# PATHOS_FPGA_Power.net
KiCad netlist of a schematic drawn in Altium Designer
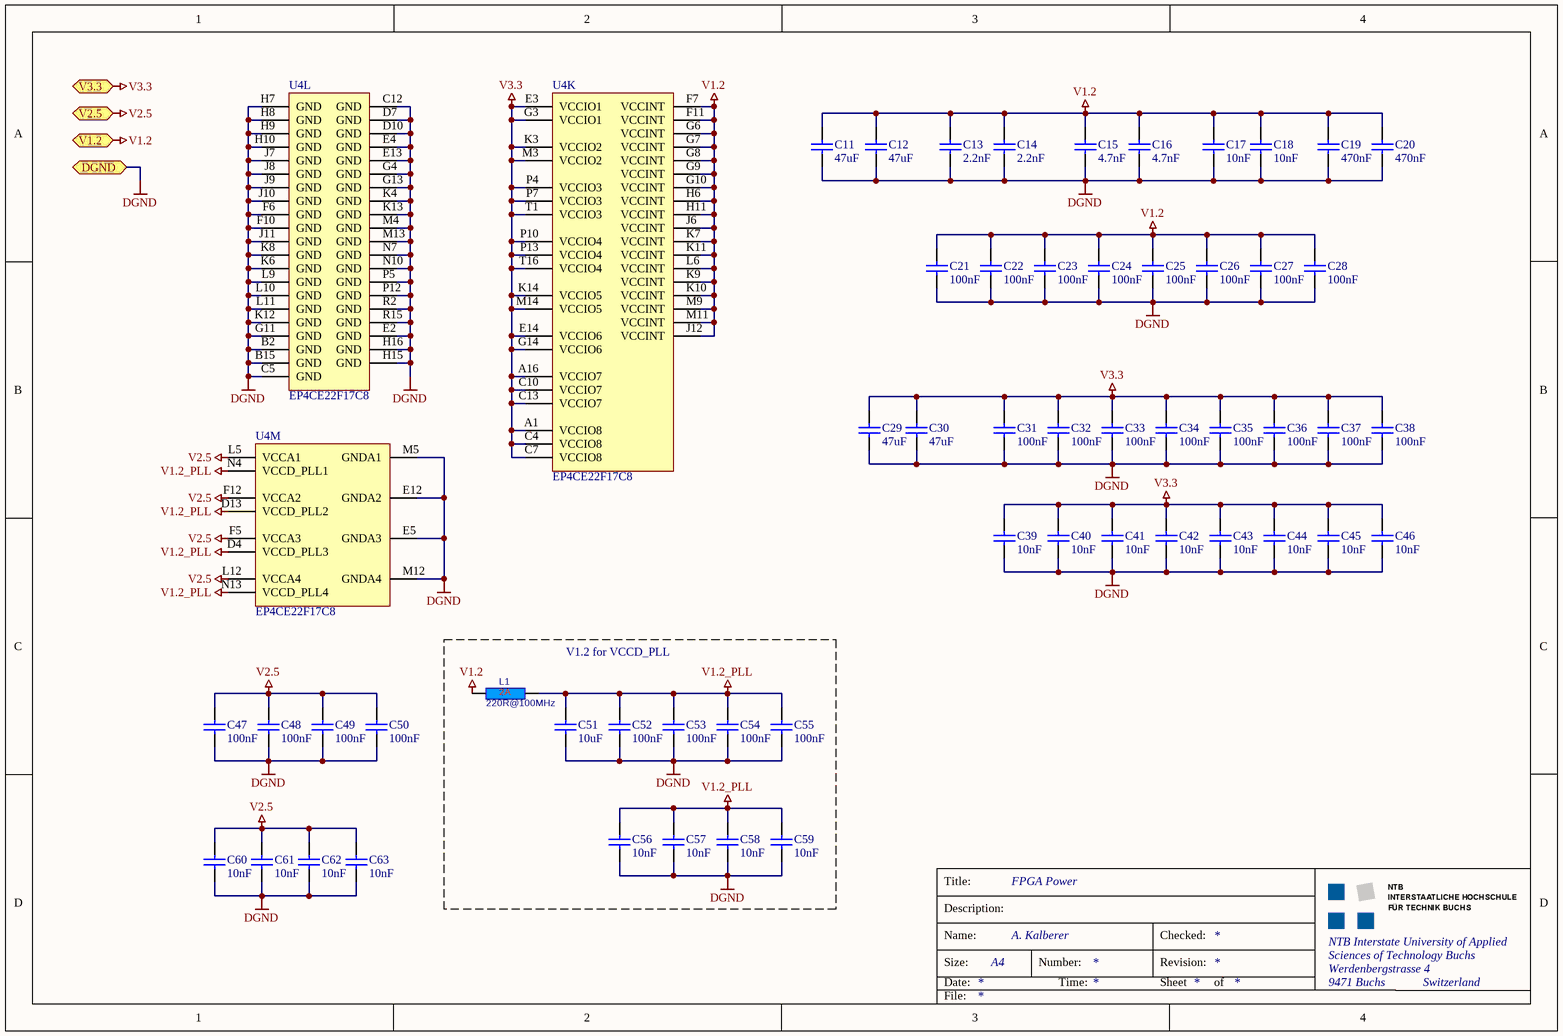
[diagram p0: PATHOS_FPGA_Power.SchDoc]

(export (version "E")
  (design (tool "Eeschema 10.0.6"))
  (components
    (comp (ref "C11")
      (value "47uF")
      (footprint "0805_3D")
      (description "Capacitor")
      (fields (field (name "#PUBLISHER") "Dr. A. Heinzelmann"))
      (libsource (lib "EFS_Sensorboard") (part "C"))
    )
    (comp (ref "C12")
      (value "47uF")
      (footprint "0805_3D")
      (description "Capacitor")
      (fields (field (name "#PUBLISHER") "Dr. A. Heinzelmann"))
      (libsource (lib "EFS_Sensorboard") (part "C"))
    )
    (comp (ref "C13")
      (value "2.2nF")
      (footprint "0402_3D")
      (description "Capacitor")
      (fields (field (name "#PUBLISHER") "Dr. A. Heinzelmann"))
      (libsource (lib "EFS_Sensorboard") (part "C"))
    )
    (comp (ref "C14")
      (value "2.2nF")
      (footprint "0402_3D")
      (description "Capacitor")
      (fields (field (name "#PUBLISHER") "Dr. A. Heinzelmann"))
      (libsource (lib "EFS_Sensorboard") (part "C"))
    )
    (comp (ref "C15")
      (value "4.7nF")
      (footprint "0402_3D")
      (description "Capacitor")
      (fields (field (name "#PUBLISHER") "Dr. A. Heinzelmann"))
      (libsource (lib "EFS_Sensorboard") (part "C"))
    )
    (comp (ref "C16")
      (value "4.7nF")
      (footprint "0402_3D")
      (description "Capacitor")
      (fields (field (name "#PUBLISHER") "Dr. A. Heinzelmann"))
      (libsource (lib "EFS_Sensorboard") (part "C"))
    )
    (comp (ref "C17")
      (value "10nF")
      (footprint "0402_3D")
      (description "Capacitor")
      (fields (field (name "#PUBLISHER") "Dr. A. Heinzelmann"))
      (libsource (lib "EFS_Sensorboard") (part "C"))
    )
    (comp (ref "C18")
      (value "10nF")
      (footprint "0402_3D")
      (description "Capacitor")
      (fields (field (name "#PUBLISHER") "Dr. A. Heinzelmann"))
      (libsource (lib "EFS_Sensorboard") (part "C"))
    )
    (comp (ref "C19")
      (value "470nF")
      (footprint "0603_3D")
      (description "Capacitor")
      (fields (field (name "#PUBLISHER") "Dr. A. Heinzelmann"))
      (libsource (lib "EFS_Sensorboard") (part "C"))
    )
    (comp (ref "C20")
      (value "470nF")
      (footprint "0603_3D")
      (description "Capacitor")
      (fields (field (name "#PUBLISHER") "Dr. A. Heinzelmann"))
      (libsource (lib "EFS_Sensorboard") (part "C"))
    )
    (comp (ref "C21")
      (value "100nF")
      (footprint "0402_3D")
      (description "Capacitor")
      (fields (field (name "#PUBLISHER") "Dr. A. Heinzelmann"))
      (libsource (lib "EFS_Sensorboard") (part "C"))
    )
    (comp (ref "C22")
      (value "100nF")
      (footprint "0402_3D")
      (description "Capacitor")
      (fields (field (name "#PUBLISHER") "Dr. A. Heinzelmann"))
      (libsource (lib "EFS_Sensorboard") (part "C"))
    )
    (comp (ref "C23")
      (value "100nF")
      (footprint "0402_3D")
      (description "Capacitor")
      (fields (field (name "#PUBLISHER") "Dr. A. Heinzelmann"))
      (libsource (lib "EFS_Sensorboard") (part "C"))
    )
    (comp (ref "C24")
      (value "100nF")
      (footprint "0402_3D")
      (description "Capacitor")
      (fields (field (name "#PUBLISHER") "Dr. A. Heinzelmann"))
      (libsource (lib "EFS_Sensorboard") (part "C"))
    )
    (comp (ref "C25")
      (value "100nF")
      (footprint "0402_3D")
      (description "Capacitor")
      (fields (field (name "#PUBLISHER") "Dr. A. Heinzelmann"))
      (libsource (lib "EFS_Sensorboard") (part "C"))
    )
    (comp (ref "C26")
      (value "100nF")
      (footprint "0402_3D")
      (description "Capacitor")
      (fields (field (name "#PUBLISHER") "Dr. A. Heinzelmann"))
      (libsource (lib "EFS_Sensorboard") (part "C"))
    )
    (comp (ref "C27")
      (value "100nF")
      (footprint "0402_3D")
      (description "Capacitor")
      (fields (field (name "#PUBLISHER") "Dr. A. Heinzelmann"))
      (libsource (lib "EFS_Sensorboard") (part "C"))
    )
    (comp (ref "C28")
      (value "100nF")
      (footprint "0402_3D")
      (description "Capacitor")
      (fields (field (name "#PUBLISHER") "Dr. A. Heinzelmann"))
      (libsource (lib "EFS_Sensorboard") (part "C"))
    )
    (comp (ref "C29")
      (value "47uF")
      (footprint "0805_3D")
      (description "Capacitor")
      (fields (field (name "#PUBLISHER") "Dr. A. Heinzelmann"))
      (libsource (lib "EFS_Sensorboard") (part "C"))
    )
    (comp (ref "C30")
      (value "47uF")
      (footprint "0805_3D")
      (description "Capacitor")
      (fields (field (name "#PUBLISHER") "Dr. A. Heinzelmann"))
      (libsource (lib "EFS_Sensorboard") (part "C"))
    )
    (comp (ref "C31")
      (value "100nF")
      (footprint "0402_3D")
      (description "Capacitor")
      (fields (field (name "#PUBLISHER") "Dr. A. Heinzelmann"))
      (libsource (lib "EFS_Sensorboard") (part "C"))
    )
    (comp (ref "C32")
      (value "100nF")
      (footprint "0402_3D")
      (description "Capacitor")
      (fields (field (name "#PUBLISHER") "Dr. A. Heinzelmann"))
      (libsource (lib "EFS_Sensorboard") (part "C"))
    )
    (comp (ref "C33")
      (value "100nF")
      (footprint "0402_3D")
      (description "Capacitor")
      (fields (field (name "#PUBLISHER") "Dr. A. Heinzelmann"))
      (libsource (lib "EFS_Sensorboard") (part "C"))
    )
    (comp (ref "C34")
      (value "100nF")
      (footprint "0402_3D")
      (description "Capacitor")
      (fields (field (name "#PUBLISHER") "Dr. A. Heinzelmann"))
      (libsource (lib "EFS_Sensorboard") (part "C"))
    )
    (comp (ref "C35")
      (value "100nF")
      (footprint "0402_3D")
      (description "Capacitor")
      (fields (field (name "#PUBLISHER") "Dr. A. Heinzelmann"))
      (libsource (lib "EFS_Sensorboard") (part "C"))
    )
    (comp (ref "C36")
      (value "100nF")
      (footprint "0402_3D")
      (description "Capacitor")
      (fields (field (name "#PUBLISHER") "Dr. A. Heinzelmann"))
      (libsource (lib "EFS_Sensorboard") (part "C"))
    )
    (comp (ref "C37")
      (value "100nF")
      (footprint "0402_3D")
      (description "Capacitor")
      (fields (field (name "#PUBLISHER") "Dr. A. Heinzelmann"))
      (libsource (lib "EFS_Sensorboard") (part "C"))
    )
    (comp (ref "C38")
      (value "100nF")
      (footprint "0402_3D")
      (description "Capacitor")
      (fields (field (name "#PUBLISHER") "Dr. A. Heinzelmann"))
      (libsource (lib "EFS_Sensorboard") (part "C"))
    )
    (comp (ref "C39")
      (value "10nF")
      (footprint "0402_3D")
      (description "Capacitor")
      (fields (field (name "#PUBLISHER") "Dr. A. Heinzelmann"))
      (libsource (lib "EFS_Sensorboard") (part "C"))
    )
    (comp (ref "C40")
      (value "10nF")
      (footprint "0402_3D")
      (description "Capacitor")
      (fields (field (name "#PUBLISHER") "Dr. A. Heinzelmann"))
      (libsource (lib "EFS_Sensorboard") (part "C"))
    )
    (comp (ref "C41")
      (value "10nF")
      (footprint "0402_3D")
      (description "Capacitor")
      (fields (field (name "#PUBLISHER") "Dr. A. Heinzelmann"))
      (libsource (lib "EFS_Sensorboard") (part "C"))
    )
    (comp (ref "C42")
      (value "10nF")
      (footprint "0402_3D")
      (description "Capacitor")
      (fields (field (name "#PUBLISHER") "Dr. A. Heinzelmann"))
      (libsource (lib "EFS_Sensorboard") (part "C"))
    )
    (comp (ref "C43")
      (value "10nF")
      (footprint "0402_3D")
      (description "Capacitor")
      (fields (field (name "#PUBLISHER") "Dr. A. Heinzelmann"))
      (libsource (lib "EFS_Sensorboard") (part "C"))
    )
    (comp (ref "C44")
      (value "10nF")
      (footprint "0402_3D")
      (description "Capacitor")
      (fields (field (name "#PUBLISHER") "Dr. A. Heinzelmann"))
      (libsource (lib "EFS_Sensorboard") (part "C"))
    )
    (comp (ref "C45")
      (value "10nF")
      (footprint "0402_3D")
      (description "Capacitor")
      (fields (field (name "#PUBLISHER") "Dr. A. Heinzelmann"))
      (libsource (lib "EFS_Sensorboard") (part "C"))
    )
    (comp (ref "C46")
      (value "10nF")
      (footprint "0402_3D")
      (description "Capacitor")
      (fields (field (name "#PUBLISHER") "Dr. A. Heinzelmann"))
      (libsource (lib "EFS_Sensorboard") (part "C"))
    )
    (comp (ref "C47")
      (value "100nF")
      (footprint "0402_3D")
      (description "Capacitor")
      (fields (field (name "#PUBLISHER") "Dr. A. Heinzelmann"))
      (libsource (lib "EFS_Sensorboard") (part "C"))
    )
    (comp (ref "C48")
      (value "100nF")
      (footprint "0402_3D")
      (description "Capacitor")
      (fields (field (name "#PUBLISHER") "Dr. A. Heinzelmann"))
      (libsource (lib "EFS_Sensorboard") (part "C"))
    )
    (comp (ref "C49")
      (value "100nF")
      (footprint "0402_3D")
      (description "Capacitor")
      (fields (field (name "#PUBLISHER") "Dr. A. Heinzelmann"))
      (libsource (lib "EFS_Sensorboard") (part "C"))
    )
    (comp (ref "C50")
      (value "100nF")
      (footprint "0402_3D")
      (description "Capacitor")
      (fields (field (name "#PUBLISHER") "Dr. A. Heinzelmann"))
      (libsource (lib "EFS_Sensorboard") (part "C"))
    )
    (comp (ref "C51")
      (value "10uF")
      (footprint "0603_3D")
      (description "Capacitor")
      (fields (field (name "#PUBLISHER") "Dr. A. Heinzelmann"))
      (libsource (lib "EFS_Sensorboard") (part "C"))
    )
    (comp (ref "C52")
      (value "100nF")
      (footprint "0402_3D")
      (description "Capacitor")
      (fields (field (name "#PUBLISHER") "Dr. A. Heinzelmann"))
      (libsource (lib "EFS_Sensorboard") (part "C"))
    )
    (comp (ref "C53")
      (value "100nF")
      (footprint "0402_3D")
      (description "Capacitor")
      (fields (field (name "#PUBLISHER") "Dr. A. Heinzelmann"))
      (libsource (lib "EFS_Sensorboard") (part "C"))
    )
    (comp (ref "C54")
      (value "100nF")
      (footprint "0402_3D")
      (description "Capacitor")
      (fields (field (name "#PUBLISHER") "Dr. A. Heinzelmann"))
      (libsource (lib "EFS_Sensorboard") (part "C"))
    )
    (comp (ref "C55")
      (value "100nF")
      (footprint "0402_3D")
      (description "Capacitor")
      (fields (field (name "#PUBLISHER") "Dr. A. Heinzelmann"))
      (libsource (lib "EFS_Sensorboard") (part "C"))
    )
    (comp (ref "C56")
      (value "10nF")
      (footprint "0402_3D")
      (description "Capacitor")
      (fields (field (name "#PUBLISHER") "Dr. A. Heinzelmann"))
      (libsource (lib "EFS_Sensorboard") (part "C"))
    )
    (comp (ref "C57")
      (value "10nF")
      (footprint "0402_3D")
      (description "Capacitor")
      (fields (field (name "#PUBLISHER") "Dr. A. Heinzelmann"))
      (libsource (lib "EFS_Sensorboard") (part "C"))
    )
    (comp (ref "C58")
      (value "10nF")
      (footprint "0402_3D")
      (description "Capacitor")
      (fields (field (name "#PUBLISHER") "Dr. A. Heinzelmann"))
      (libsource (lib "EFS_Sensorboard") (part "C"))
    )
    (comp (ref "C59")
      (value "10nF")
      (footprint "0402_3D")
      (description "Capacitor")
      (fields (field (name "#PUBLISHER") "Dr. A. Heinzelmann"))
      (libsource (lib "EFS_Sensorboard") (part "C"))
    )
    (comp (ref "C60")
      (value "10nF")
      (footprint "0402_3D")
      (description "Capacitor")
      (fields (field (name "#PUBLISHER") "Dr. A. Heinzelmann"))
      (libsource (lib "EFS_Sensorboard") (part "C"))
    )
    (comp (ref "C61")
      (value "10nF")
      (footprint "0402_3D")
      (description "Capacitor")
      (fields (field (name "#PUBLISHER") "Dr. A. Heinzelmann"))
      (libsource (lib "EFS_Sensorboard") (part "C"))
    )
    (comp (ref "C62")
      (value "10nF")
      (footprint "0402_3D")
      (description "Capacitor")
      (fields (field (name "#PUBLISHER") "Dr. A. Heinzelmann"))
      (libsource (lib "EFS_Sensorboard") (part "C"))
    )
    (comp (ref "C63")
      (value "10nF")
      (footprint "0402_3D")
      (description "Capacitor")
      (fields (field (name "#PUBLISHER") "Dr. A. Heinzelmann"))
      (libsource (lib "EFS_Sensorboard") (part "C"))
    )
    (comp (ref "L1")
      (value "220R@100MHz")
      (footprint "0603_3D")
      (description "220R@100MHz 2A EMI FILTER")
      (fields (field (name "TOLERANCE") "25%"))
      (libsource (lib "Viola") (part "L-220R@100MHz-2A-25%-0603"))
    )
    (comp (ref "U4")
      (value "EP4CE22F17C8")
      (footprint "FBGA256")
      (fields (field (name "PUBLISHER") "Altium Limited"))
      (libsource (lib "EFS_Sensorboard") (part "EP4CE22F17C8"))
    )
  )
  (nets
    (net (code "1") (name "DGND") (class "Default")
      (node (ref "C11") (pin "1") (pinfunction "1_1") (pintype "passive"))
      (node (ref "C12") (pin "1") (pinfunction "1_1") (pintype "passive"))
      (node (ref "C13") (pin "1") (pinfunction "1_1") (pintype "passive"))
      (node (ref "C14") (pin "1") (pinfunction "1_1") (pintype "passive"))
      (node (ref "C15") (pin "1") (pinfunction "1_1") (pintype "passive"))
      (node (ref "C16") (pin "1") (pinfunction "1_1") (pintype "passive"))
      (node (ref "C17") (pin "1") (pinfunction "1_1") (pintype "passive"))
      (node (ref "C18") (pin "1") (pinfunction "1_1") (pintype "passive"))
      (node (ref "C19") (pin "1") (pinfunction "1_1") (pintype "passive"))
      (node (ref "C20") (pin "1") (pinfunction "1_1") (pintype "passive"))
      (node (ref "C21") (pin "1") (pinfunction "1_1") (pintype "passive"))
      (node (ref "C22") (pin "1") (pinfunction "1_1") (pintype "passive"))
      (node (ref "C23") (pin "1") (pinfunction "1_1") (pintype "passive"))
      (node (ref "C24") (pin "1") (pinfunction "1_1") (pintype "passive"))
      (node (ref "C25") (pin "1") (pinfunction "1_1") (pintype "passive"))
      (node (ref "C26") (pin "1") (pinfunction "1_1") (pintype "passive"))
      (node (ref "C27") (pin "1") (pinfunction "1_1") (pintype "passive"))
      (node (ref "C28") (pin "1") (pinfunction "1_1") (pintype "passive"))
      (node (ref "C29") (pin "1") (pinfunction "1_1") (pintype "passive"))
      (node (ref "C30") (pin "1") (pinfunction "1_1") (pintype "passive"))
      (node (ref "C31") (pin "1") (pinfunction "1_1") (pintype "passive"))
      (node (ref "C32") (pin "1") (pinfunction "1_1") (pintype "passive"))
      (node (ref "C33") (pin "1") (pinfunction "1_1") (pintype "passive"))
      (node (ref "C34") (pin "1") (pinfunction "1_1") (pintype "passive"))
      (node (ref "C35") (pin "1") (pinfunction "1_1") (pintype "passive"))
      (node (ref "C36") (pin "1") (pinfunction "1_1") (pintype "passive"))
      (node (ref "C37") (pin "1") (pinfunction "1_1") (pintype "passive"))
      (node (ref "C38") (pin "1") (pinfunction "1_1") (pintype "passive"))
      (node (ref "C39") (pin "1") (pinfunction "1_1") (pintype "passive"))
      (node (ref "C40") (pin "1") (pinfunction "1_1") (pintype "passive"))
      (node (ref "C41") (pin "1") (pinfunction "1_1") (pintype "passive"))
      (node (ref "C42") (pin "1") (pinfunction "1_1") (pintype "passive"))
      (node (ref "C43") (pin "1") (pinfunction "1_1") (pintype "passive"))
      (node (ref "C44") (pin "1") (pinfunction "1_1") (pintype "passive"))
      (node (ref "C45") (pin "1") (pinfunction "1_1") (pintype "passive"))
      (node (ref "C46") (pin "1") (pinfunction "1_1") (pintype "passive"))
      (node (ref "C47") (pin "1") (pinfunction "1_1") (pintype "passive"))
      (node (ref "C48") (pin "1") (pinfunction "1_1") (pintype "passive"))
      (node (ref "C49") (pin "1") (pinfunction "1_1") (pintype "passive"))
      (node (ref "C50") (pin "1") (pinfunction "1_1") (pintype "passive"))
      (node (ref "C51") (pin "1") (pinfunction "1_1") (pintype "passive"))
      (node (ref "C52") (pin "1") (pinfunction "1_1") (pintype "passive"))
      (node (ref "C53") (pin "1") (pinfunction "1_1") (pintype "passive"))
      (node (ref "C54") (pin "1") (pinfunction "1_1") (pintype "passive"))
      (node (ref "C55") (pin "1") (pinfunction "1_1") (pintype "passive"))
      (node (ref "C56") (pin "1") (pinfunction "1_1") (pintype "passive"))
      (node (ref "C57") (pin "1") (pinfunction "1_1") (pintype "passive"))
      (node (ref "C58") (pin "1") (pinfunction "1_1") (pintype "passive"))
      (node (ref "C59") (pin "1") (pinfunction "1_1") (pintype "passive"))
      (node (ref "C60") (pin "1") (pinfunction "1_1") (pintype "passive"))
      (node (ref "C61") (pin "1") (pinfunction "1_1") (pintype "passive"))
      (node (ref "C62") (pin "1") (pinfunction "1_1") (pintype "passive"))
      (node (ref "C63") (pin "1") (pinfunction "1_1") (pintype "passive"))
      (node (ref "U4") (pin "B15") (pinfunction "GND_B15") (pintype "power_in"))
      (node (ref "U4") (pin "B2") (pinfunction "GND_B2") (pintype "power_in"))
      (node (ref "U4") (pin "C12") (pinfunction "GND_C12") (pintype "power_in"))
      (node (ref "U4") (pin "C5") (pinfunction "GND_C5") (pintype "power_in"))
      (node (ref "U4") (pin "D10") (pinfunction "GND_D10") (pintype "power_in"))
      (node (ref "U4") (pin "D7") (pinfunction "GND_D7") (pintype "power_in"))
      (node (ref "U4") (pin "E12") (pinfunction "GNDA2_E12") (pintype "power_in"))
      (node (ref "U4") (pin "E13") (pinfunction "GND_E13") (pintype "power_in"))
      (node (ref "U4") (pin "E2") (pinfunction "GND_E2") (pintype "power_in"))
      (node (ref "U4") (pin "E4") (pinfunction "GND_E4") (pintype "power_in"))
      (node (ref "U4") (pin "E5") (pinfunction "GNDA3_E5") (pintype "power_in"))
      (node (ref "U4") (pin "F10") (pinfunction "GND_F10") (pintype "power_in"))
      (node (ref "U4") (pin "F6") (pinfunction "GND_F6") (pintype "power_in"))
      (node (ref "U4") (pin "G11") (pinfunction "GND_G11") (pintype "power_in"))
      (node (ref "U4") (pin "G13") (pinfunction "GND_G13") (pintype "power_in"))
      (node (ref "U4") (pin "G4") (pinfunction "GND_G4") (pintype "power_in"))
      (node (ref "U4") (pin "H10") (pinfunction "GND_H10") (pintype "power_in"))
      (node (ref "U4") (pin "H15") (pinfunction "GND_H15") (pintype "power_in"))
      (node (ref "U4") (pin "H16") (pinfunction "GND_H16") (pintype "power_in"))
      (node (ref "U4") (pin "H7") (pinfunction "GND_H7") (pintype "power_in"))
      (node (ref "U4") (pin "H8") (pinfunction "GND_H8") (pintype "power_in"))
      (node (ref "U4") (pin "H9") (pinfunction "GND_H9") (pintype "power_in"))
      (node (ref "U4") (pin "J10") (pinfunction "GND_J10") (pintype "power_in"))
      (node (ref "U4") (pin "J11") (pinfunction "GND_J11") (pintype "power_in"))
      (node (ref "U4") (pin "J7") (pinfunction "GND_J7") (pintype "power_in"))
      (node (ref "U4") (pin "J8") (pinfunction "GND_J8") (pintype "power_in"))
      (node (ref "U4") (pin "J9") (pinfunction "GND_J9") (pintype "power_in"))
      (node (ref "U4") (pin "K12") (pinfunction "GND_K12") (pintype "power_in"))
      (node (ref "U4") (pin "K13") (pinfunction "GND_K13") (pintype "power_in"))
      (node (ref "U4") (pin "K4") (pinfunction "GND_K4") (pintype "power_in"))
      (node (ref "U4") (pin "K6") (pinfunction "GND_K6") (pintype "power_in"))
      (node (ref "U4") (pin "K8") (pinfunction "GND_K8") (pintype "power_in"))
      (node (ref "U4") (pin "L10") (pinfunction "GND_L10") (pintype "power_in"))
      (node (ref "U4") (pin "L11") (pinfunction "GND_L11") (pintype "power_in"))
      (node (ref "U4") (pin "L9") (pinfunction "GND_L9") (pintype "power_in"))
      (node (ref "U4") (pin "M12") (pinfunction "GNDA4_M12") (pintype "power_in"))
      (node (ref "U4") (pin "M13") (pinfunction "GND_M13") (pintype "power_in"))
      (node (ref "U4") (pin "M4") (pinfunction "GND_M4") (pintype "power_in"))
      (node (ref "U4") (pin "M5") (pinfunction "GNDA1_M5") (pintype "power_in"))
      (node (ref "U4") (pin "N10") (pinfunction "GND_N10") (pintype "power_in"))
      (node (ref "U4") (pin "N7") (pinfunction "GND_N7") (pintype "power_in"))
      (node (ref "U4") (pin "P12") (pinfunction "GND_P12") (pintype "power_in"))
      (node (ref "U4") (pin "P5") (pinfunction "GND_P5") (pintype "power_in"))
      (node (ref "U4") (pin "R15") (pinfunction "GND_R15") (pintype "power_in"))
      (node (ref "U4") (pin "R2") (pinfunction "GND_R2") (pintype "power_in"))
    )
    (net (code "2") (name "V1.2") (class "Default")
      (node (ref "C11") (pin "2") (pinfunction "2_2") (pintype "passive"))
      (node (ref "C12") (pin "2") (pinfunction "2_2") (pintype "passive"))
      (node (ref "C13") (pin "2") (pinfunction "2_2") (pintype "passive"))
      (node (ref "C14") (pin "2") (pinfunction "2_2") (pintype "passive"))
      (node (ref "C15") (pin "2") (pinfunction "2_2") (pintype "passive"))
      (node (ref "C16") (pin "2") (pinfunction "2_2") (pintype "passive"))
      (node (ref "C17") (pin "2") (pinfunction "2_2") (pintype "passive"))
      (node (ref "C18") (pin "2") (pinfunction "2_2") (pintype "passive"))
      (node (ref "C19") (pin "2") (pinfunction "2_2") (pintype "passive"))
      (node (ref "C20") (pin "2") (pinfunction "2_2") (pintype "passive"))
      (node (ref "C21") (pin "2") (pinfunction "2_2") (pintype "passive"))
      (node (ref "C22") (pin "2") (pinfunction "2_2") (pintype "passive"))
      (node (ref "C23") (pin "2") (pinfunction "2_2") (pintype "passive"))
      (node (ref "C24") (pin "2") (pinfunction "2_2") (pintype "passive"))
      (node (ref "C25") (pin "2") (pinfunction "2_2") (pintype "passive"))
      (node (ref "C26") (pin "2") (pinfunction "2_2") (pintype "passive"))
      (node (ref "C27") (pin "2") (pinfunction "2_2") (pintype "passive"))
      (node (ref "C28") (pin "2") (pinfunction "2_2") (pintype "passive"))
      (node (ref "L1") (pin "1") (pinfunction "1_1") (pintype "passive"))
      (node (ref "U4") (pin "F11") (pinfunction "VCCINT_F11") (pintype "power_in"))
      (node (ref "U4") (pin "F7") (pinfunction "VCCINT_F7") (pintype "power_in"))
      (node (ref "U4") (pin "G10") (pinfunction "VCCINT_G10") (pintype "power_in"))
      (node (ref "U4") (pin "G6") (pinfunction "VCCINT_G6") (pintype "power_in"))
      (node (ref "U4") (pin "G7") (pinfunction "VCCINT_G7") (pintype "power_in"))
      (node (ref "U4") (pin "G8") (pinfunction "VCCINT_G8") (pintype "power_in"))
      (node (ref "U4") (pin "G9") (pinfunction "VCCINT_G9") (pintype "power_in"))
      (node (ref "U4") (pin "H11") (pinfunction "VCCINT_H11") (pintype "power_in"))
      (node (ref "U4") (pin "H6") (pinfunction "VCCINT_H6") (pintype "power_in"))
      (node (ref "U4") (pin "J12") (pinfunction "VCCINT_J12") (pintype "power_in"))
      (node (ref "U4") (pin "J6") (pinfunction "VCCINT_J6") (pintype "power_in"))
      (node (ref "U4") (pin "K10") (pinfunction "VCCINT_K10") (pintype "power_in"))
      (node (ref "U4") (pin "K11") (pinfunction "VCCINT_K11") (pintype "power_in"))
      (node (ref "U4") (pin "K7") (pinfunction "VCCINT_K7") (pintype "power_in"))
      (node (ref "U4") (pin "K9") (pinfunction "VCCINT_K9") (pintype "power_in"))
      (node (ref "U4") (pin "L6") (pinfunction "VCCINT_L6") (pintype "power_in"))
      (node (ref "U4") (pin "M11") (pinfunction "VCCINT_M11") (pintype "power_in"))
      (node (ref "U4") (pin "M9") (pinfunction "VCCINT_M9") (pintype "power_in"))
    )
    (net (code "3") (name "V1.2_PLL") (class "Default")
      (node (ref "C51") (pin "2") (pinfunction "2_2") (pintype "passive"))
      (node (ref "C52") (pin "2") (pinfunction "2_2") (pintype "passive"))
      (node (ref "C53") (pin "2") (pinfunction "2_2") (pintype "passive"))
      (node (ref "C54") (pin "2") (pinfunction "2_2") (pintype "passive"))
      (node (ref "C55") (pin "2") (pinfunction "2_2") (pintype "passive"))
      (node (ref "C56") (pin "2") (pinfunction "2_2") (pintype "passive"))
      (node (ref "C57") (pin "2") (pinfunction "2_2") (pintype "passive"))
      (node (ref "C58") (pin "2") (pinfunction "2_2") (pintype "passive"))
      (node (ref "C59") (pin "2") (pinfunction "2_2") (pintype "passive"))
      (node (ref "L1") (pin "2") (pinfunction "2_2") (pintype "passive"))
      (node (ref "U4") (pin "D13") (pinfunction "VCCD_PLL2_D13") (pintype "power_in"))
      (node (ref "U4") (pin "D4") (pinfunction "VCCD_PLL3_D4") (pintype "power_in"))
      (node (ref "U4") (pin "N13") (pinfunction "VCCD_PLL4_N13") (pintype "power_in"))
      (node (ref "U4") (pin "N4") (pinfunction "VCCD_PLL1_N4") (pintype "power_in"))
    )
    (net (code "4") (name "V2.5") (class "Default")
      (node (ref "C47") (pin "2") (pinfunction "2_2") (pintype "passive"))
      (node (ref "C48") (pin "2") (pinfunction "2_2") (pintype "passive"))
      (node (ref "C49") (pin "2") (pinfunction "2_2") (pintype "passive"))
      (node (ref "C50") (pin "2") (pinfunction "2_2") (pintype "passive"))
      (node (ref "C60") (pin "2") (pinfunction "2_2") (pintype "passive"))
      (node (ref "C61") (pin "2") (pinfunction "2_2") (pintype "passive"))
      (node (ref "C62") (pin "2") (pinfunction "2_2") (pintype "passive"))
      (node (ref "C63") (pin "2") (pinfunction "2_2") (pintype "passive"))
      (node (ref "U4") (pin "F12") (pinfunction "VCCA2_F12") (pintype "power_in"))
      (node (ref "U4") (pin "F5") (pinfunction "VCCA3_F5") (pintype "power_in"))
      (node (ref "U4") (pin "L12") (pinfunction "VCCA4_L12") (pintype "power_in"))
      (node (ref "U4") (pin "L5") (pinfunction "VCCA1_L5") (pintype "power_in"))
    )
    (net (code "5") (name "V3.3") (class "Default")
      (node (ref "C29") (pin "2") (pinfunction "2_2") (pintype "passive"))
      (node (ref "C30") (pin "2") (pinfunction "2_2") (pintype "passive"))
      (node (ref "C31") (pin "2") (pinfunction "2_2") (pintype "passive"))
      (node (ref "C32") (pin "2") (pinfunction "2_2") (pintype "passive"))
      (node (ref "C33") (pin "2") (pinfunction "2_2") (pintype "passive"))
      (node (ref "C34") (pin "2") (pinfunction "2_2") (pintype "passive"))
      (node (ref "C35") (pin "2") (pinfunction "2_2") (pintype "passive"))
      (node (ref "C36") (pin "2") (pinfunction "2_2") (pintype "passive"))
      (node (ref "C37") (pin "2") (pinfunction "2_2") (pintype "passive"))
      (node (ref "C38") (pin "2") (pinfunction "2_2") (pintype "passive"))
      (node (ref "C39") (pin "2") (pinfunction "2_2") (pintype "passive"))
      (node (ref "C40") (pin "2") (pinfunction "2_2") (pintype "passive"))
      (node (ref "C41") (pin "2") (pinfunction "2_2") (pintype "passive"))
      (node (ref "C42") (pin "2") (pinfunction "2_2") (pintype "passive"))
      (node (ref "C43") (pin "2") (pinfunction "2_2") (pintype "passive"))
      (node (ref "C44") (pin "2") (pinfunction "2_2") (pintype "passive"))
      (node (ref "C45") (pin "2") (pinfunction "2_2") (pintype "passive"))
      (node (ref "C46") (pin "2") (pinfunction "2_2") (pintype "passive"))
      (node (ref "U4") (pin "A1") (pinfunction "VCCIO8_A1") (pintype "power_in"))
      (node (ref "U4") (pin "A16") (pinfunction "VCCIO7_A16") (pintype "power_in"))
      (node (ref "U4") (pin "C10") (pinfunction "VCCIO7_C10") (pintype "power_in"))
      (node (ref "U4") (pin "C13") (pinfunction "VCCIO7_C13") (pintype "power_in"))
      (node (ref "U4") (pin "C4") (pinfunction "VCCIO8_C4") (pintype "power_in"))
      (node (ref "U4") (pin "C7") (pinfunction "VCCIO8_C7") (pintype "power_in"))
      (node (ref "U4") (pin "E14") (pinfunction "VCCIO6_E14") (pintype "power_in"))
      (node (ref "U4") (pin "E3") (pinfunction "VCCIO1_E3") (pintype "power_in"))
      (node (ref "U4") (pin "G14") (pinfunction "VCCIO6_G14") (pintype "power_in"))
      (node (ref "U4") (pin "G3") (pinfunction "VCCIO1_G3") (pintype "power_in"))
      (node (ref "U4") (pin "K14") (pinfunction "VCCIO5_K14") (pintype "power_in"))
      (node (ref "U4") (pin "K3") (pinfunction "VCCIO2_K3") (pintype "power_in"))
      (node (ref "U4") (pin "M14") (pinfunction "VCCIO5_M14") (pintype "power_in"))
      (node (ref "U4") (pin "M3") (pinfunction "VCCIO2_M3") (pintype "power_in"))
      (node (ref "U4") (pin "P10") (pinfunction "VCCIO4_P10") (pintype "power_in"))
      (node (ref "U4") (pin "P13") (pinfunction "VCCIO4_P13") (pintype "power_in"))
      (node (ref "U4") (pin "P4") (pinfunction "VCCIO3_P4") (pintype "power_in"))
      (node (ref "U4") (pin "P7") (pinfunction "VCCIO3_P7") (pintype "power_in"))
      (node (ref "U4") (pin "T1") (pinfunction "VCCIO3_T1") (pintype "power_in"))
      (node (ref "U4") (pin "T16") (pinfunction "VCCIO4_T16") (pintype "power_in"))
    )
  )
)
